# WiFi_MBUS_Reader.net
KiCad netlist of a schematic drawn in EAGLE
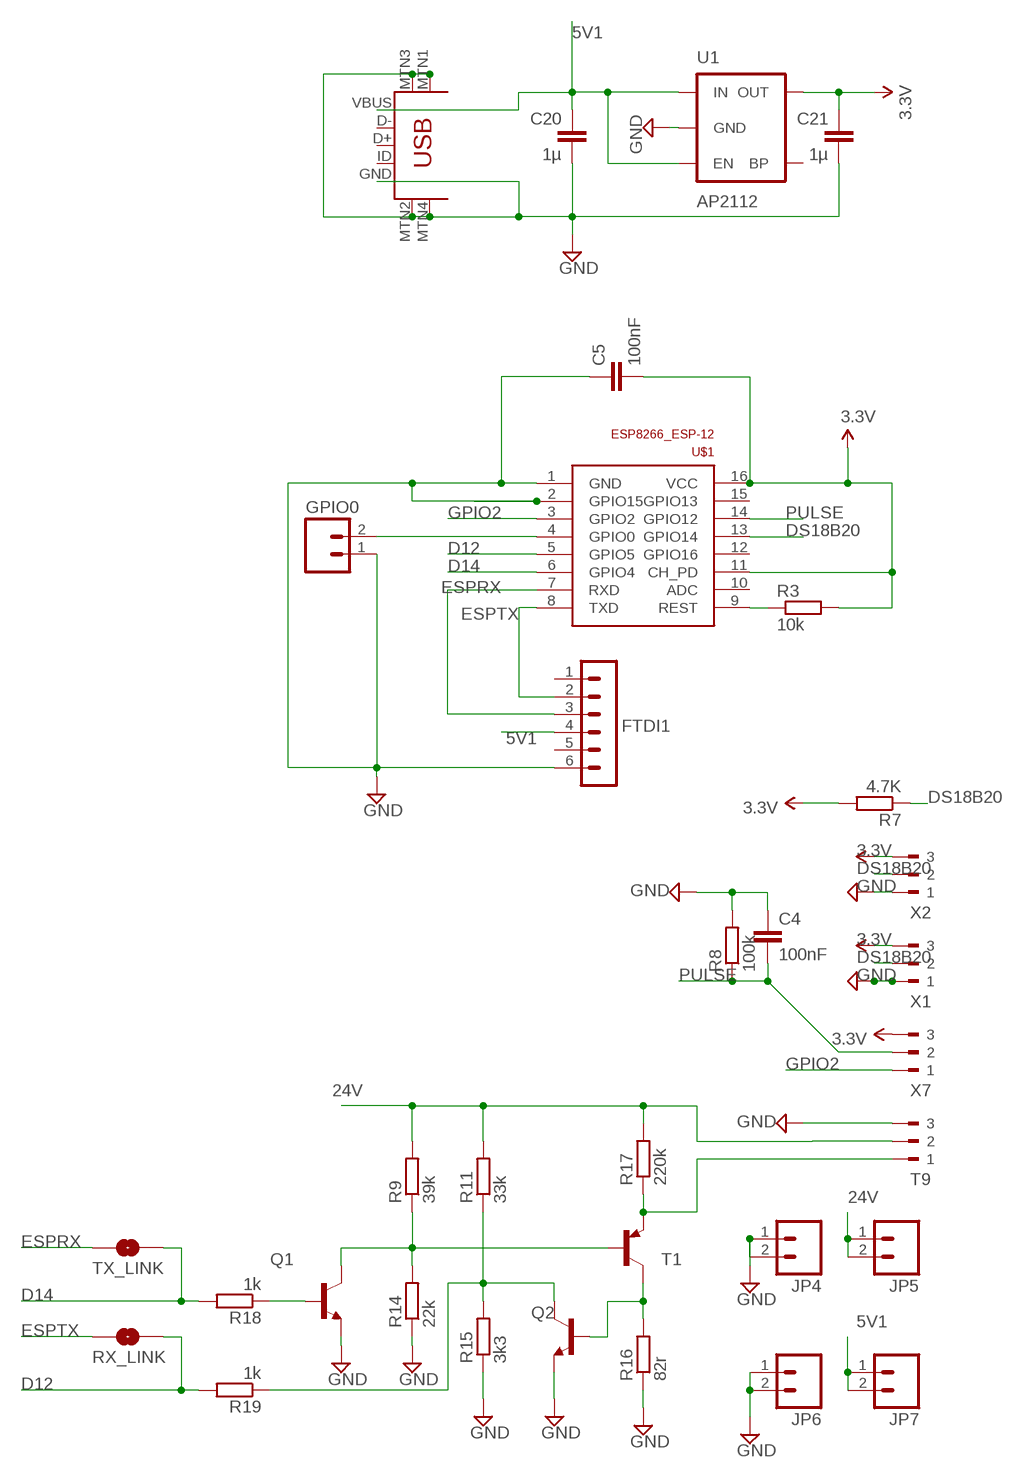
[diagram p0: schematic, sheet 1]

(export (version "E")
  (design (tool "Eeschema 10.0.6"))
  (components
    (comp (ref "C4")
      (value "100nF")
      (footprint "eagle-import:C0603")
      (libsource (lib "eagle-import") (part "C-EUC0603"))
    )
    (comp (ref "C5")
      (value "100nF")
      (footprint "eagle-import:C0603")
      (libsource (lib "eagle-import") (part "C-EUC0603"))
    )
    (comp (ref "C20")
      (value "1µ")
      (footprint "eagle-import:C0603")
      (libsource (lib "eagle-import") (part "C-EUC0603"))
    )
    (comp (ref "C21")
      (value "1µ")
      (footprint "eagle-import:C0603")
      (libsource (lib "eagle-import") (part "C-EUC0603"))
    )
    (comp (ref "FTDI1")
      (value "FTDI")
      (footprint "eagle-import:MA06-1")
      (libsource (lib "eagle-import") (part "MA06-1"))
    )
    (comp (ref "GPIO0")
      (value "M02PTH")
      (footprint "eagle-import:1X02")
      (libsource (lib "eagle-import") (part "M02PTH"))
    )
    (comp (ref "JP4")
      (value "M02PTH")
      (footprint "eagle-import:1X02")
      (libsource (lib "eagle-import") (part "M02PTH"))
    )
    (comp (ref "JP5")
      (value "M02PTH")
      (footprint "eagle-import:1X02")
      (libsource (lib "eagle-import") (part "M02PTH"))
    )
    (comp (ref "JP6")
      (value "M02PTH")
      (footprint "eagle-import:1X02")
      (libsource (lib "eagle-import") (part "M02PTH"))
    )
    (comp (ref "JP7")
      (value "M02PTH")
      (footprint "eagle-import:1X02")
      (libsource (lib "eagle-import") (part "M02PTH"))
    )
    (comp (ref "Q1")
      (value "BC808-NPN-SOT23-BEC")
      (footprint "eagle-import:SOT23-BEC")
      (libsource (lib "eagle-import") (part "-NPN-SOT23-BECBC808"))
    )
    (comp (ref "Q2")
      (value "BC808-NPN-SOT23-BEC")
      (footprint "eagle-import:SOT23-BEC")
      (libsource (lib "eagle-import") (part "-NPN-SOT23-BECBC808"))
    )
    (comp (ref "R3")
      (value "10k")
      (footprint "eagle-import:R0603")
      (libsource (lib "eagle-import") (part "R-EU_R0603"))
    )
    (comp (ref "R7")
      (value "4.7K")
      (footprint "eagle-import:R0603")
      (libsource (lib "eagle-import") (part "R-EU_R0603"))
    )
    (comp (ref "R8")
      (value "100k")
      (footprint "eagle-import:R0603")
      (libsource (lib "eagle-import") (part "R-EU_R0603"))
    )
    (comp (ref "R9")
      (value "39k")
      (footprint "eagle-import:R0603")
      (libsource (lib "eagle-import") (part "R-EU_R0603"))
    )
    (comp (ref "R11")
      (value "33k")
      (footprint "eagle-import:R0603")
      (libsource (lib "eagle-import") (part "R-EU_R0603"))
    )
    (comp (ref "R14")
      (value "22k")
      (footprint "eagle-import:R0603")
      (libsource (lib "eagle-import") (part "R-EU_R0603"))
    )
    (comp (ref "R15")
      (value "3k3")
      (footprint "eagle-import:R0603")
      (libsource (lib "eagle-import") (part "R-EU_R0603"))
    )
    (comp (ref "R16")
      (value "82r")
      (footprint "eagle-import:R0603")
      (libsource (lib "eagle-import") (part "R-EU_R0603"))
    )
    (comp (ref "R17")
      (value "220k")
      (footprint "eagle-import:R0603")
      (libsource (lib "eagle-import") (part "R-EU_R0603"))
    )
    (comp (ref "R18")
      (value "1k")
      (footprint "eagle-import:R0603")
      (libsource (lib "eagle-import") (part "R-EU_R0603"))
    )
    (comp (ref "R19")
      (value "1k")
      (footprint "eagle-import:R0603")
      (libsource (lib "eagle-import") (part "R-EU_R0603"))
    )
    (comp (ref "RX_LINK")
      (value "SOLDERJUMPERNO")
      (footprint "eagle-import:SJ_2S-NO")
      (libsource (lib "eagle-import") (part "SOLDERJUMPERNO"))
    )
    (comp (ref "T1")
      (value "BC807-16-PNP-SOT23-BEC")
      (footprint "eagle-import:SOT23-BEC")
      (libsource (lib "eagle-import") (part "-PNP-SOT23-BECBC807-16"))
    )
    (comp (ref "T9")
      (value "180-3")
      (footprint "eagle-import:180-3")
      (libsource (lib "eagle-import") (part "180-3"))
    )
    (comp (ref "TX_LINK")
      (value "SOLDERJUMPERNO")
      (footprint "eagle-import:SJ_2S-NO")
      (libsource (lib "eagle-import") (part "SOLDERJUMPERNO"))
    )
    (comp (ref "U$1")
      (value "ESP8266_ESP-12")
      (footprint "eagle-import:ESP8266-ESP12")
      (libsource (lib "eagle-import") (part "ESP8266_ESP-12"))
    )
    (comp (ref "U$10")
      (value "USB-MINIB-5PIN")
      (footprint "eagle-import:USB-MINIB-CISECO")
      (libsource (lib "eagle-import") (part "USB-MINIB-5PIN"))
    )
    (comp (ref "U1")
      (value "AP2112")
      (footprint "eagle-import:SOT23-5")
      (libsource (lib "eagle-import") (part "V_REG_LDOSMD"))
    )
    (comp (ref "X1")
      (value "180-3")
      (footprint "eagle-import:180-3")
      (libsource (lib "eagle-import") (part "180-3"))
    )
    (comp (ref "X2")
      (value "180-3")
      (footprint "eagle-import:180-3")
      (libsource (lib "eagle-import") (part "180-3"))
    )
    (comp (ref "X7")
      (value "180-3")
      (footprint "eagle-import:180-3")
      (libsource (lib "eagle-import") (part "180-3"))
    )
  )
  (nets
    (net (code "1") (name "/5V1") (class "Default")
      (node (ref "C20") (pin "1") (pinfunction "1_1") (pintype "passive"))
      (node (ref "FTDI1") (pin "4") (pinfunction "4_4") (pintype "passive"))
      (node (ref "JP7") (pin "1") (pinfunction "1_1") (pintype "passive"))
      (node (ref "JP7") (pin "2") (pinfunction "2_2") (pintype "passive"))
      (node (ref "U$10") (pin "VBUS") (pinfunction "VBUS_VBUS") (pintype "bidirectional"))
      (node (ref "U1") (pin "1") (pinfunction "IN_1") (pintype "input"))
      (node (ref "U1") (pin "3") (pinfunction "EN_3") (pintype "input"))
    )
    (net (code "2") (name "/24V") (class "Default")
      (node (ref "JP5") (pin "1") (pinfunction "1_1") (pintype "passive"))
      (node (ref "JP5") (pin "2") (pinfunction "2_2") (pintype "passive"))
      (node (ref "R11") (pin "2") (pinfunction "2_2") (pintype "passive"))
      (node (ref "R17") (pin "2") (pinfunction "2_2") (pintype "passive"))
      (node (ref "R9") (pin "2") (pinfunction "2_2") (pintype "passive"))
      (node (ref "T9") (pin "2") (pinfunction "2_2") (pintype "passive"))
    )
    (net (code "3") (name "/D12") (class "Default")
      (node (ref "R19") (pin "2") (pinfunction "2_2") (pintype "passive"))
      (node (ref "RX_LINK") (pin "2") (pinfunction "2_2") (pintype "passive"))
      (node (ref "U$1") (pin "5") (pinfunction "GPIO5_5") (pintype "bidirectional"))
    )
    (net (code "4") (name "/D14") (class "Default")
      (node (ref "R18") (pin "2") (pinfunction "2_2") (pintype "passive"))
      (node (ref "TX_LINK") (pin "2") (pinfunction "2_2") (pintype "passive"))
      (node (ref "U$1") (pin "6") (pinfunction "GPIO4_6") (pintype "bidirectional"))
    )
    (net (code "5") (name "/DS18B20") (class "Default")
      (node (ref "R7") (pin "1") (pinfunction "1_1") (pintype "passive"))
      (node (ref "U$1") (pin "13") (pinfunction "GPIO14_13") (pintype "bidirectional"))
      (node (ref "X1") (pin "2") (pinfunction "2_2") (pintype "passive"))
      (node (ref "X2") (pin "2") (pinfunction "2_2") (pintype "passive"))
    )
    (net (code "6") (name "/ESPRX") (class "Default")
      (node (ref "FTDI1") (pin "3") (pinfunction "3_3") (pintype "passive"))
      (node (ref "TX_LINK") (pin "1") (pinfunction "1_1") (pintype "passive"))
      (node (ref "U$1") (pin "7") (pinfunction "RXD_7") (pintype "bidirectional"))
    )
    (net (code "7") (name "/ESPTX") (class "Default")
      (node (ref "FTDI1") (pin "2") (pinfunction "2_2") (pintype "passive"))
      (node (ref "RX_LINK") (pin "1") (pinfunction "1_1") (pintype "passive"))
      (node (ref "U$1") (pin "8") (pinfunction "TXD_8") (pintype "bidirectional"))
    )
    (net (code "8") (name "/GPIO2") (class "Default")
      (node (ref "U$1") (pin "3") (pinfunction "GPIO2_3") (pintype "bidirectional"))
      (node (ref "X7") (pin "1") (pinfunction "1_1") (pintype "passive"))
    )
    (net (code "9") (name "/PULSE") (class "Default")
      (node (ref "C4") (pin "2") (pinfunction "2_2") (pintype "passive"))
      (node (ref "R8") (pin "1") (pinfunction "1_1") (pintype "passive"))
      (node (ref "U$1") (pin "14") (pinfunction "GPIO12_14") (pintype "bidirectional"))
      (node (ref "X7") (pin "2") (pinfunction "2_2") (pintype "passive"))
    )
    (net (code "10") (name "3.3V") (class "Default")
      (node (ref "C21") (pin "1") (pinfunction "1_1") (pintype "passive"))
      (node (ref "C5") (pin "2") (pinfunction "2_2") (pintype "passive"))
      (node (ref "R3") (pin "2") (pinfunction "2_2") (pintype "passive"))
      (node (ref "R7") (pin "2") (pinfunction "2_2") (pintype "passive"))
      (node (ref "U$1") (pin "11") (pinfunction "CH_PD_11") (pintype "bidirectional"))
      (node (ref "U$1") (pin "16") (pinfunction "VCC_16") (pintype "bidirectional"))
      (node (ref "U1") (pin "5") (pinfunction "OUT_5") (pintype "passive"))
      (node (ref "X1") (pin "3") (pinfunction "3_3") (pintype "passive"))
      (node (ref "X2") (pin "3") (pinfunction "3_3") (pintype "passive"))
      (node (ref "X7") (pin "3") (pinfunction "3_3") (pintype "passive"))
    )
    (net (code "11") (name "GND") (class "Default")
      (node (ref "C20") (pin "2") (pinfunction "2_2") (pintype "passive"))
      (node (ref "C21") (pin "2") (pinfunction "2_2") (pintype "passive"))
      (node (ref "C4") (pin "1") (pinfunction "1_1") (pintype "passive"))
      (node (ref "C5") (pin "1") (pinfunction "1_1") (pintype "passive"))
      (node (ref "FTDI1") (pin "6") (pinfunction "6_6") (pintype "passive"))
      (node (ref "GPIO0") (pin "1") (pinfunction "1_1") (pintype "passive"))
      (node (ref "JP4") (pin "1") (pinfunction "1_1") (pintype "passive"))
      (node (ref "JP4") (pin "2") (pinfunction "2_2") (pintype "passive"))
      (node (ref "JP6") (pin "1") (pinfunction "1_1") (pintype "passive"))
      (node (ref "JP6") (pin "2") (pinfunction "2_2") (pintype "passive"))
      (node (ref "Q1") (pin "E") (pinfunction "E_E") (pintype "passive"))
      (node (ref "Q2") (pin "E") (pinfunction "E_E") (pintype "passive"))
      (node (ref "R14") (pin "1") (pinfunction "1_1") (pintype "passive"))
      (node (ref "R15") (pin "1") (pinfunction "1_1") (pintype "passive"))
      (node (ref "R16") (pin "1") (pinfunction "1_1") (pintype "passive"))
      (node (ref "R8") (pin "2") (pinfunction "2_2") (pintype "passive"))
      (node (ref "T9") (pin "3") (pinfunction "3_3") (pintype "passive"))
      (node (ref "U$1") (pin "1") (pinfunction "GND_1") (pintype "bidirectional"))
      (node (ref "U$1") (pin "2") (pinfunction "GPIO15_2") (pintype "bidirectional"))
      (node (ref "U$10") (pin "GND") (pinfunction "GND_GND") (pintype "bidirectional"))
      (node (ref "U$10") (pin "MTN1") (pinfunction "MTN2_MTN1") (pintype "bidirectional"))
      (node (ref "U$10") (pin "MTN2") (pinfunction "MTN3_MTN2") (pintype "bidirectional"))
      (node (ref "U$10") (pin "MTN3") (pinfunction "MTN1_MTN3") (pintype "bidirectional"))
      (node (ref "U$10") (pin "MTN4") (pinfunction "MTN4_MTN4") (pintype "bidirectional"))
      (node (ref "U1") (pin "2") (pinfunction "GND_2") (pintype "input"))
      (node (ref "X1") (pin "1") (pinfunction "1_1") (pintype "passive"))
      (node (ref "X2") (pin "1") (pinfunction "1_1") (pintype "passive"))
    )
    (net (code "12") (name "Net-(Q1-PadB)") (class "Default")
      (node (ref "Q1") (pin "B") (pinfunction "B_B") (pintype "passive"))
      (node (ref "R18") (pin "1") (pinfunction "1_1") (pintype "passive"))
    )
    (net (code "13") (name "Net-(Q1-PadC)") (class "Default")
      (node (ref "Q1") (pin "C") (pinfunction "C_C") (pintype "passive"))
      (node (ref "R14") (pin "2") (pinfunction "2_2") (pintype "passive"))
      (node (ref "R9") (pin "1") (pinfunction "1_1") (pintype "passive"))
      (node (ref "T1") (pin "B") (pinfunction "B_B") (pintype "passive"))
    )
    (net (code "14") (name "Net-(Q2-PadB)") (class "Default")
      (node (ref "Q2") (pin "B") (pinfunction "B_B") (pintype "passive"))
      (node (ref "R16") (pin "2") (pinfunction "2_2") (pintype "passive"))
      (node (ref "T1") (pin "C") (pinfunction "C_C") (pintype "passive"))
    )
    (net (code "15") (name "Net-(Q2-PadC)") (class "Default")
      (node (ref "Q2") (pin "C") (pinfunction "C_C") (pintype "passive"))
      (node (ref "R11") (pin "1") (pinfunction "1_1") (pintype "passive"))
      (node (ref "R15") (pin "2") (pinfunction "2_2") (pintype "passive"))
      (node (ref "R19") (pin "1") (pinfunction "1_1") (pintype "passive"))
    )
    (net (code "16") (name "Net-(R17-Pad1)") (class "Default")
      (node (ref "R17") (pin "1") (pinfunction "1_1") (pintype "passive"))
      (node (ref "T1") (pin "E") (pinfunction "E_E") (pintype "passive"))
      (node (ref "T9") (pin "1") (pinfunction "1_1") (pintype "passive"))
    )
    (net (code "17") (name "Net-(U$1-GPIO0)") (class "Default")
      (node (ref "GPIO0") (pin "2") (pinfunction "2_2") (pintype "passive"))
      (node (ref "U$1") (pin "4") (pinfunction "GPIO0_4") (pintype "bidirectional"))
    )
    (net (code "18") (name "Net-(U$1-REST)") (class "Default")
      (node (ref "R3") (pin "1") (pinfunction "1_1") (pintype "passive"))
      (node (ref "U$1") (pin "9") (pinfunction "REST_9") (pintype "bidirectional"))
    )
    (net (code "19") (name "unconnected-(FTDI1-Pad1)") (class "Default")
      (node (ref "FTDI1") (pin "1") (pinfunction "1_1") (pintype "passive"))
    )
    (net (code "20") (name "unconnected-(FTDI1-Pad5)") (class "Default")
      (node (ref "FTDI1") (pin "5") (pinfunction "5_5") (pintype "passive"))
    )
    (net (code "21") (name "unconnected-(U$1-ADC-Pad10)") (class "Default")
      (node (ref "U$1") (pin "10") (pinfunction "ADC_10") (pintype "bidirectional"))
    )
    (net (code "22") (name "unconnected-(U$1-GPIO13-Pad15)") (class "Default")
      (node (ref "U$1") (pin "15") (pinfunction "GPIO13_15") (pintype "bidirectional"))
    )
    (net (code "23") (name "unconnected-(U$1-GPIO16-Pad12)") (class "Default")
      (node (ref "U$1") (pin "12") (pinfunction "GPIO16_12") (pintype "bidirectional"))
    )
    (net (code "24") (name "unconnected-(U$10-PadD+)") (class "Default")
      (node (ref "U$10") (pin "D+") (pinfunction "D+_D+") (pintype "bidirectional"))
    )
    (net (code "25") (name "unconnected-(U$10-PadD-)") (class "Default")
      (node (ref "U$10") (pin "D-") (pinfunction "D-_D-") (pintype "bidirectional"))
    )
    (net (code "26") (name "unconnected-(U$10-PadID)") (class "Default")
      (node (ref "U$10") (pin "ID") (pinfunction "ID_ID") (pintype "bidirectional"))
    )
    (net (code "27") (name "unconnected-(U1-BP-Pad4)") (class "Default")
      (node (ref "U1") (pin "4") (pinfunction "BP_4") (pintype "input"))
    )
  )
)
